# LDO.net
KiCad netlist of a schematic drawn in Altium Designer
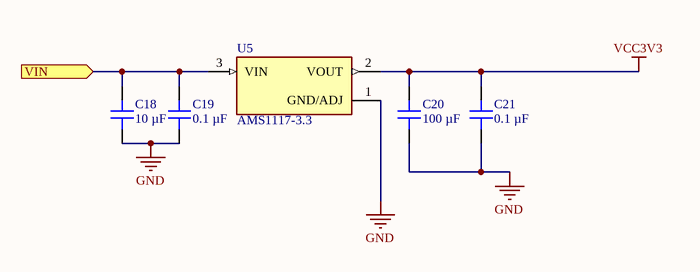
[diagram p0: LDO.SchDoc]

(export (version "E")
  (design (tool "Eeschema 10.0.6"))
  (components
    (comp (ref "C18")
      (value "10 µF")
      (footprint "CAP 0805_2012")
      (description "CAP CER 10UF 16V X6S 0805")
      (fields
        (field (name "PART NUMBER") "C2012X6S1C106K125AC")
        (field (name "MANUFACTURER") "TDK Corporation")
      )
      (libsource (lib "Celestial Altium Library - altium_library") (part "Capacitor"))
    )
    (comp (ref "C19")
      (value "0.1 µF")
      (footprint "CAP 0805_2012")
      (description "CAP CER 0.1UF 50V X7R 0805")
      (fields (field (name "PART NUMBER") "CC0805MRX7R9BB104") (field (name "MANUFACTURER") "Yageo"))
      (libsource (lib "Celestial Altium Library - altium_library") (part "Capacitor"))
    )
    (comp (ref "C20")
      (value "100 µF")
      (footprint "CAP 0805_2012")
      (description "CAP CER 100UF 2.5V X5R 0805")
      (fields (field (name "PART NUMBER") "PMK212BBJ107MG-T") (field (name "MANUFACTURER") "Taiyo Yuden"))
      (libsource (lib "Celestial Altium Library - altium_library") (part "Capacitor"))
    )
    (comp (ref "C21")
      (value "0.1 µF")
      (footprint "CAP 0805_2012")
      (description "CAP CER 0.1UF 50V X7R 0805")
      (fields (field (name "PART NUMBER") "CC0805MRX7R9BB104") (field (name "MANUFACTURER") "Yageo"))
      (libsource (lib "Celestial Altium Library - altium_library") (part "Capacitor"))
    )
    (comp (ref "U5")
      (value "AMS1117-3.3")
      (footprint "SOT229P700X180-4N")
      (description "Sot223/Pkg 1-Amp 3.3-Volt Low Drop Out Voltage Regulatator")
      (fields (field (name "MF") "Advanced Monolithic Systems"))
      (libsource (lib "AMS1117-3.3") (part "AMS1117-3.3"))
    )
  )
  (nets
    (net (code "1") (name "/VIN") (class "Default")
      (node (ref "C18") (pin "2") (pinfunction "2_2") (pintype "passive"))
      (node (ref "C19") (pin "2") (pinfunction "2_2") (pintype "passive"))
      (node (ref "U5") (pin "3") (pinfunction "VIN_3") (pintype "input"))
    )
    (net (code "2") (name "GND") (class "Default")
      (node (ref "C18") (pin "1") (pinfunction "1_1") (pintype "passive"))
      (node (ref "C19") (pin "1") (pinfunction "1_1") (pintype "passive"))
      (node (ref "C20") (pin "1") (pinfunction "1_1") (pintype "passive"))
      (node (ref "C21") (pin "1") (pinfunction "1_1") (pintype "passive"))
      (node (ref "U5") (pin "1") (pinfunction "GND/ADJ_1") (pintype "power_in"))
    )
    (net (code "3") (name "VCC3V3") (class "Default")
      (node (ref "C20") (pin "2") (pinfunction "2_2") (pintype "passive"))
      (node (ref "C21") (pin "2") (pinfunction "2_2") (pintype "passive"))
      (node (ref "U5") (pin "2") (pinfunction "VOUT_2") (pintype "output"))
    )
  )
)
